# main.net
KiCad netlist of a schematic drawn in EAGLE
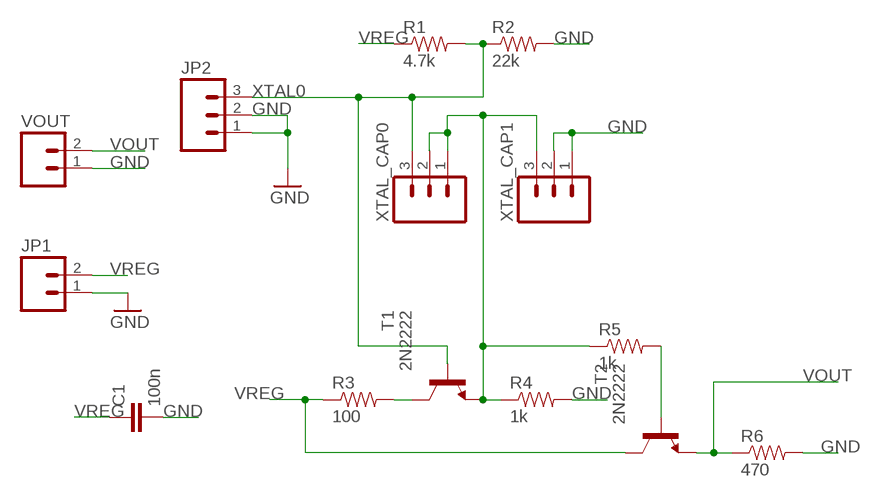
[diagram p0: schematic, sheet 1]

(export (version "E")
  (design (tool "Eeschema 10.0.6"))
  (components
    (comp (ref "C1")
      (value "100n")
      (footprint "eagle-import:CAP-PTH-SMALL")
      (libsource (lib "eagle-import") (part "CAPPTH"))
    )
    (comp (ref "JP1")
      (value "M02LOCK")
      (footprint "eagle-import:1X02_LOCK")
      (libsource (lib "eagle-import") (part "M02LOCK"))
    )
    (comp (ref "JP2")
      (value "M03LOCK")
      (footprint "eagle-import:1X03_LOCK")
      (libsource (lib "eagle-import") (part "M03LOCK"))
    )
    (comp (ref "R1")
      (value "4.7k")
      (footprint "eagle-import:AXIAL-0.4")
      (libsource (lib "eagle-import") (part "RESISTORPTH-1/4W"))
    )
    (comp (ref "R2")
      (value "22k")
      (footprint "eagle-import:AXIAL-0.4")
      (libsource (lib "eagle-import") (part "RESISTORPTH-1/4W"))
    )
    (comp (ref "R3")
      (value "100")
      (footprint "eagle-import:AXIAL-0.4")
      (libsource (lib "eagle-import") (part "RESISTORPTH-1/4W"))
    )
    (comp (ref "R4")
      (value "1k")
      (footprint "eagle-import:AXIAL-0.4")
      (libsource (lib "eagle-import") (part "RESISTORPTH-1/4W"))
    )
    (comp (ref "R5")
      (value "1k")
      (footprint "eagle-import:AXIAL-0.4")
      (libsource (lib "eagle-import") (part "RESISTORPTH-1/4W"))
    )
    (comp (ref "R6")
      (value "470")
      (footprint "eagle-import:AXIAL-0.4")
      (libsource (lib "eagle-import") (part "RESISTORPTH-1/4W"))
    )
    (comp (ref "T1")
      (value "2N2222")
      (footprint "eagle-import:TO18")
      (libsource (lib "eagle-import") (part "2N2222"))
    )
    (comp (ref "T2")
      (value "2N2222")
      (footprint "eagle-import:TO18")
      (libsource (lib "eagle-import") (part "2N2222"))
    )
    (comp (ref "VOUT")
      (value "M02LOCK")
      (footprint "eagle-import:1X02_LOCK")
      (libsource (lib "eagle-import") (part "M02LOCK"))
    )
    (comp (ref "XTAL_CAP0")
      (value "M03LOCK")
      (footprint "eagle-import:1X03_LOCK")
      (libsource (lib "eagle-import") (part "M03LOCK"))
    )
    (comp (ref "XTAL_CAP1")
      (value "M03LOCK")
      (footprint "eagle-import:1X03_LOCK")
      (libsource (lib "eagle-import") (part "M03LOCK"))
    )
  )
  (nets
    (net (code "1") (name "/VOUT") (class "Default")
      (node (ref "R6") (pin "P$1") (pinfunction "1_P$1") (pintype "passive"))
      (node (ref "T2") (pin "1") (pinfunction "E_1") (pintype "passive"))
      (node (ref "VOUT") (pin "2") (pinfunction "2_2") (pintype "passive"))
    )
    (net (code "2") (name "/VREG") (class "Default")
      (node (ref "C1") (pin "1") (pinfunction "1_1") (pintype "passive"))
      (node (ref "JP1") (pin "2") (pinfunction "2_2") (pintype "passive"))
      (node (ref "R1") (pin "P$1") (pinfunction "1_P$1") (pintype "passive"))
      (node (ref "R3") (pin "P$1") (pinfunction "1_P$1") (pintype "passive"))
      (node (ref "T2") (pin "3") (pinfunction "C_3") (pintype "passive"))
    )
    (net (code "3") (name "/XTAL0") (class "Default")
      (node (ref "JP2") (pin "3") (pinfunction "3_3") (pintype "passive"))
      (node (ref "R1") (pin "P$2") (pinfunction "2_P$2") (pintype "passive"))
      (node (ref "R2") (pin "P$1") (pinfunction "1_P$1") (pintype "passive"))
      (node (ref "T1") (pin "2") (pinfunction "B_2") (pintype "passive"))
      (node (ref "XTAL_CAP0") (pin "3") (pinfunction "3_3") (pintype "passive"))
    )
    (net (code "4") (name "GND") (class "Default")
      (node (ref "C1") (pin "2") (pinfunction "2_2") (pintype "passive"))
      (node (ref "JP1") (pin "1") (pinfunction "1_1") (pintype "passive"))
      (node (ref "JP2") (pin "1") (pinfunction "1_1") (pintype "passive"))
      (node (ref "JP2") (pin "2") (pinfunction "2_2") (pintype "passive"))
      (node (ref "R2") (pin "P$2") (pinfunction "2_P$2") (pintype "passive"))
      (node (ref "R4") (pin "P$2") (pinfunction "2_P$2") (pintype "passive"))
      (node (ref "R6") (pin "P$2") (pinfunction "2_P$2") (pintype "passive"))
      (node (ref "VOUT") (pin "1") (pinfunction "1_1") (pintype "passive"))
      (node (ref "XTAL_CAP1") (pin "1") (pinfunction "1_1") (pintype "passive"))
      (node (ref "XTAL_CAP1") (pin "2") (pinfunction "2_2") (pintype "passive"))
    )
    (net (code "5") (name "Net-(R3-2)") (class "Default")
      (node (ref "R3") (pin "P$2") (pinfunction "2_P$2") (pintype "passive"))
      (node (ref "T1") (pin "3") (pinfunction "C_3") (pintype "passive"))
    )
    (net (code "6") (name "Net-(R4-1)") (class "Default")
      (node (ref "R4") (pin "P$1") (pinfunction "1_P$1") (pintype "passive"))
      (node (ref "R5") (pin "P$1") (pinfunction "1_P$1") (pintype "passive"))
      (node (ref "T1") (pin "1") (pinfunction "E_1") (pintype "passive"))
      (node (ref "XTAL_CAP0") (pin "1") (pinfunction "1_1") (pintype "passive"))
      (node (ref "XTAL_CAP0") (pin "2") (pinfunction "2_2") (pintype "passive"))
      (node (ref "XTAL_CAP1") (pin "3") (pinfunction "3_3") (pintype "passive"))
    )
    (net (code "7") (name "Net-(R5-2)") (class "Default")
      (node (ref "R5") (pin "P$2") (pinfunction "2_P$2") (pintype "passive"))
      (node (ref "T2") (pin "2") (pinfunction "B_2") (pintype "passive"))
    )
  )
)
